# WL-FRONT.net
KiCad netlist of a schematic drawn in Altium Designer
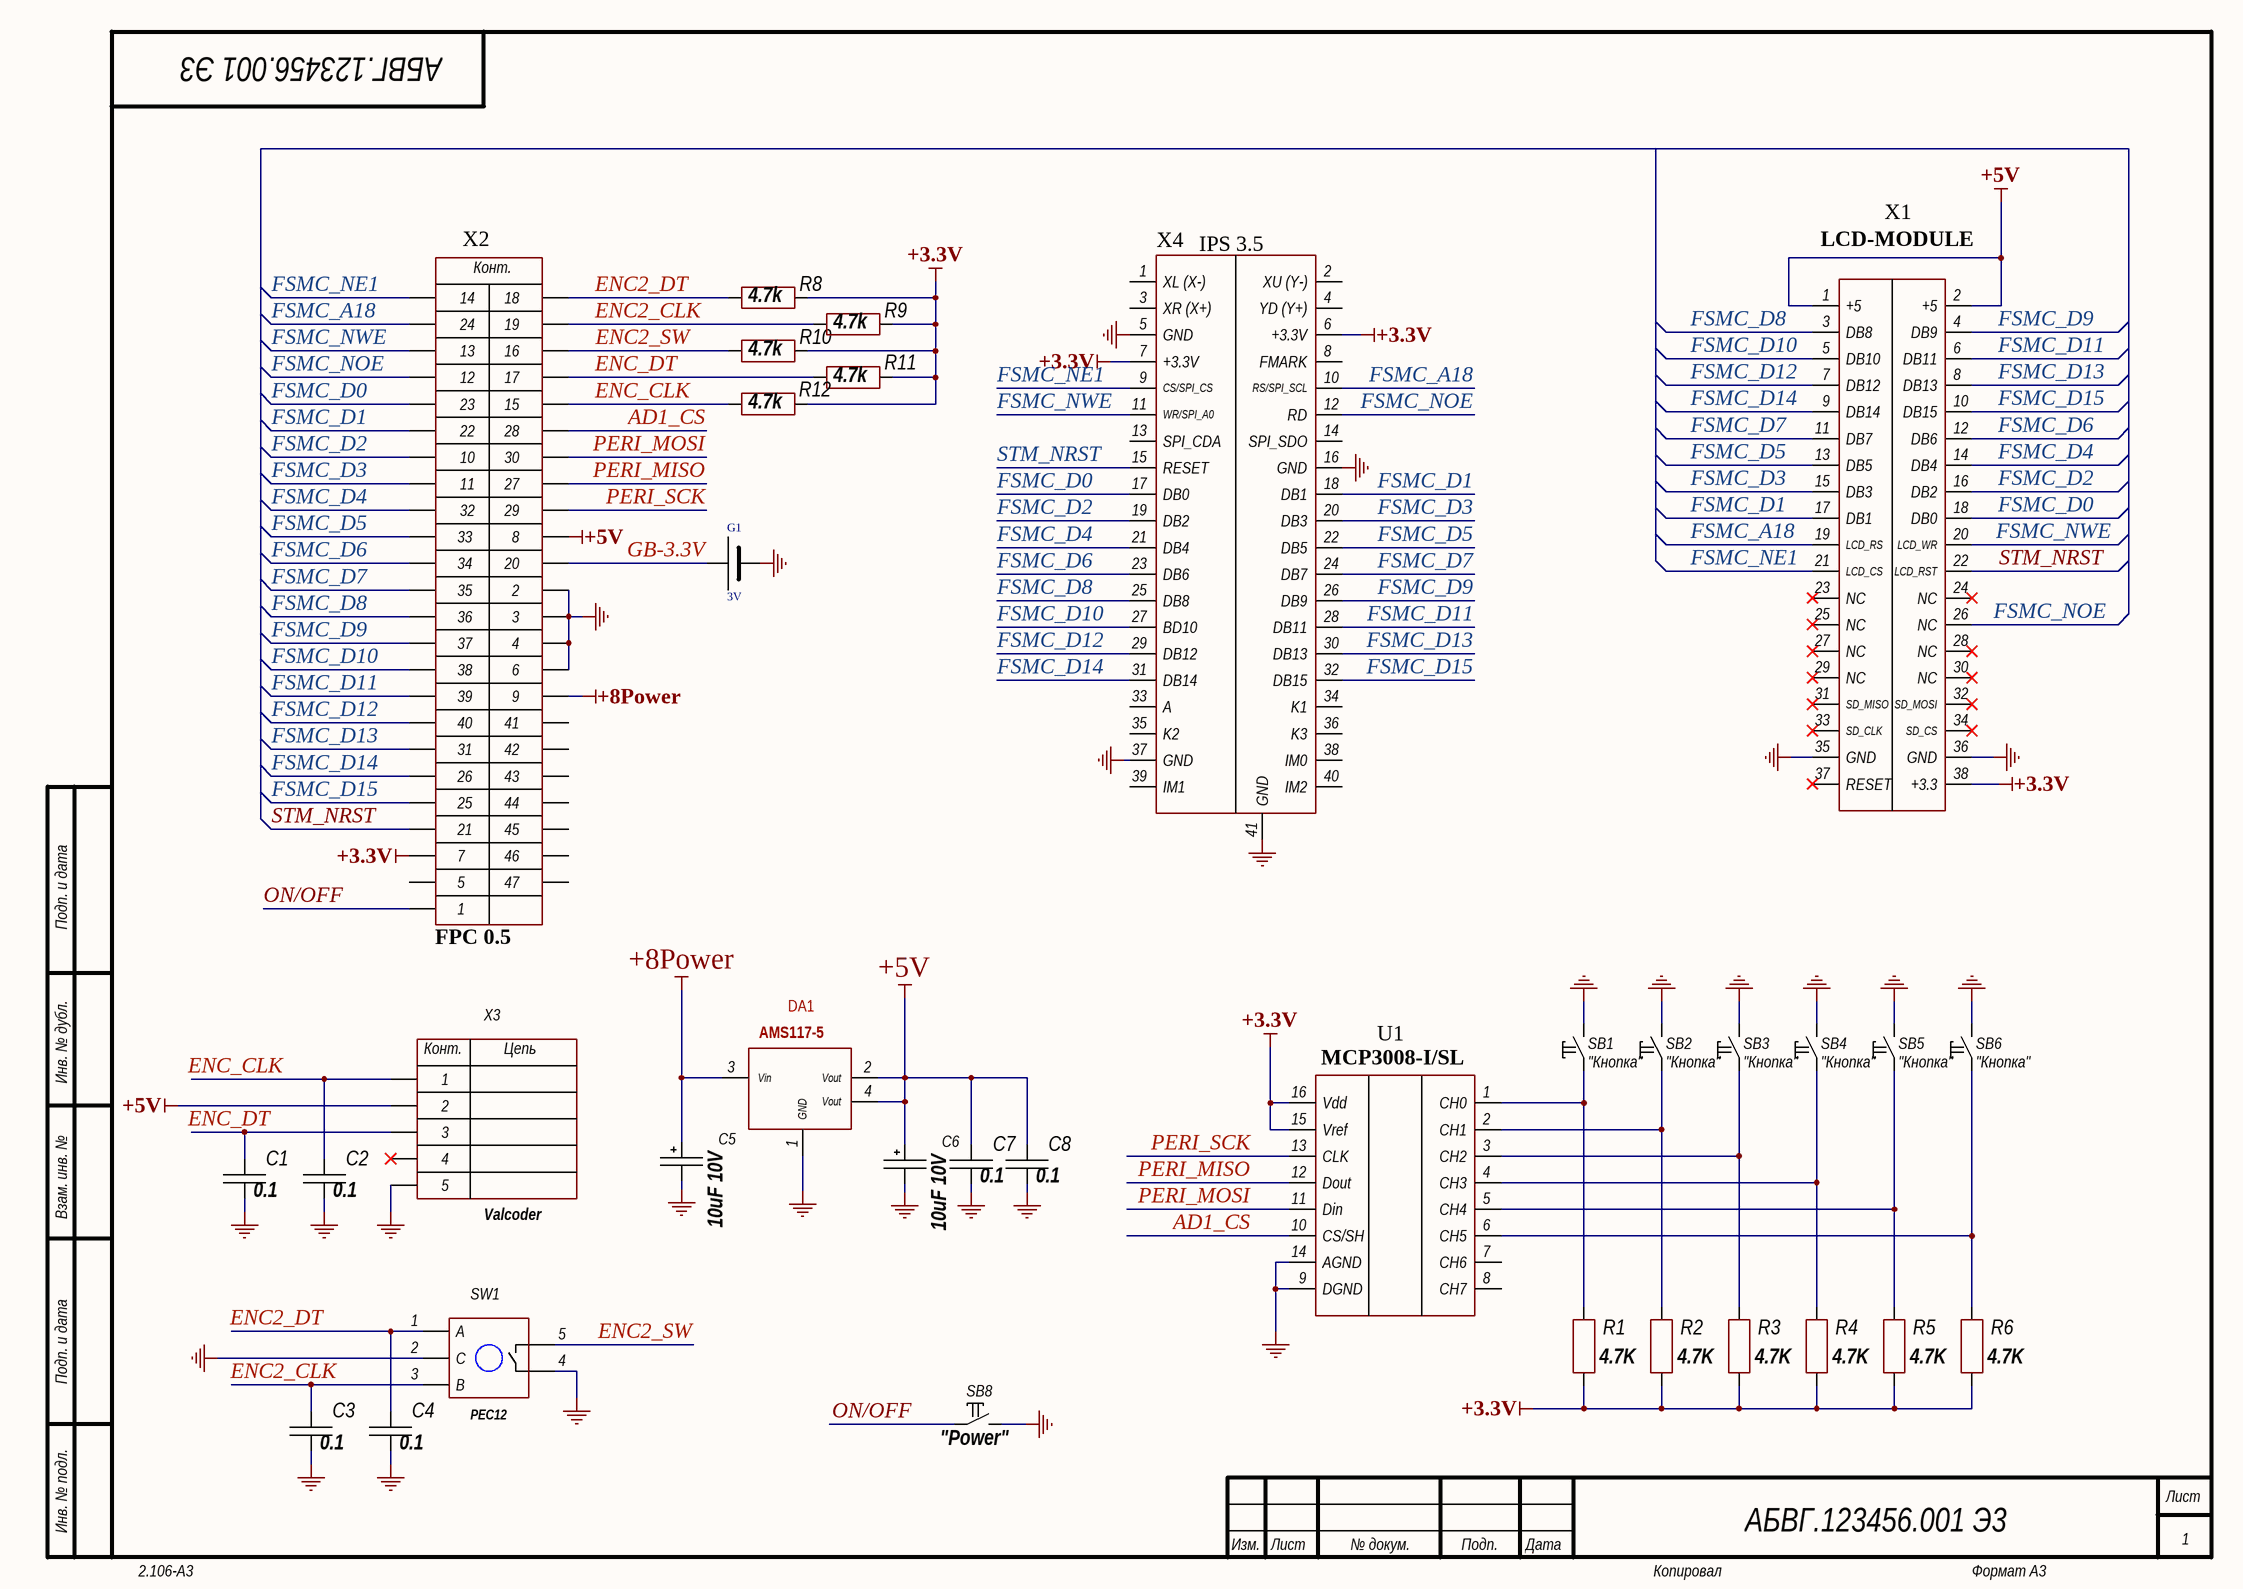
[diagram p0: WL-FRONT.SchDoc]

(export (version "E")
  (design (tool "Eeschema 10.0.6"))
  (components
    (comp (ref "C1")
      (value "0.1")
      (footprint "standard:CH0805C")
      (libsource (lib "Discrete") (part "Capacitor"))
    )
    (comp (ref "C2")
      (value "0.1")
      (footprint "standard:CH0805C")
      (libsource (lib "Discrete") (part "Capacitor"))
    )
    (comp (ref "C3")
      (value "0.1")
      (footprint "standard:CH0805C")
      (libsource (lib "Discrete") (part "Capacitor"))
    )
    (comp (ref "C4")
      (value "0.1")
      (footprint "standard:CH0805C")
      (libsource (lib "Discrete") (part "Capacitor"))
    )
    (comp (ref "C5")
      (value "10uF 10V")
      (footprint "standard:TANTAL_B")
      (libsource (lib "Discrete") (part "TantalCap"))
    )
    (comp (ref "C6")
      (value "10uF 10V")
      (footprint "standard:TANTAL_B")
      (libsource (lib "Discrete") (part "TantalCap"))
    )
    (comp (ref "C7")
      (value "0.1")
      (footprint "standard:CH0805C")
      (libsource (lib "Discrete") (part "Capacitor"))
    )
    (comp (ref "C8")
      (value "0.1")
      (footprint "standard:CH0805C")
      (libsource (lib "Discrete") (part "Capacitor"))
    )
    (comp (ref "DA1") (value "AMS117-5") (footprint "SOT223") (libsource (lib "Analog") (part "AMS117")))
    (comp (ref "G1")
      (value "3V")
      (footprint "BAT: CH224-2032")
      (libsource (lib "Connectors") (part "POWER_BAT"))
    )
    (comp (ref "R1")
      (value "4.7K")
      (footprint "standard:CH0805R")
      (libsource (lib "Discrete") (part "Resistor"))
    )
    (comp (ref "R2")
      (value "4.7K")
      (footprint "standard:CH0805R")
      (libsource (lib "Discrete") (part "Resistor"))
    )
    (comp (ref "R3") (value "4.7K") (footprint "standard:CH0805R") (libsource (lib "") (part "Resistor_2")))
    (comp (ref "R4")
      (value "4.7K")
      (footprint "standard:CH0805R")
      (libsource (lib "Discrete") (part "Resistor"))
    )
    (comp (ref "R5")
      (value "4.7K")
      (footprint "standard:CH0805R")
      (libsource (lib "Discrete") (part "Resistor"))
    )
    (comp (ref "R6")
      (value "4.7K")
      (footprint "standard:CH0805R")
      (libsource (lib "Discrete") (part "Resistor"))
    )
    (comp (ref "R8") (value "4.7k") (footprint "standard:CH0805R") (libsource (lib "") (part "Resistor_1")))
    (comp (ref "R9") (value "4.7k") (footprint "standard:CH0805R") (libsource (lib "") (part "Resistor_1")))
    (comp (ref "R10") (value "4.7k") (footprint "standard:CH0805R") (libsource (lib "") (part "Resistor_1")))
    (comp (ref "R11") (value "4.7k") (footprint "standard:CH0805R") (libsource (lib "") (part "Resistor_1")))
    (comp (ref "R12") (value "4.7k") (footprint "standard:CH0805R") (libsource (lib "") (part "Resistor_1")))
    (comp (ref "SB1")
      (value "\"Кнопка\"")
      (footprint "custom:BUT: 6x6 SMD")
      (description "6x6 mm")
      (libsource (lib "") (part "Tactile switches_1"))
    )
    (comp (ref "SB2")
      (value "\"Кнопка\"")
      (footprint "custom:BUT: 6x6 SMD")
      (description "6x6 mm")
      (libsource (lib "") (part "Tactile switches_1"))
    )
    (comp (ref "SB3")
      (value "\"Кнопка\"")
      (footprint "custom:BUT: 6x6 SMD")
      (description "6x6 mm")
      (libsource (lib "Connectors") (part "Tactile switches"))
    )
    (comp (ref "SB4")
      (value "\"Кнопка\"")
      (footprint "custom:BUT: 6x6 SMD")
      (description "6x6 mm")
      (libsource (lib "") (part "Tactile switches_1"))
    )
    (comp (ref "SB5")
      (value "\"Кнопка\"")
      (footprint "custom:BUT: 6x6 SMD")
      (description "6x6 mm")
      (libsource (lib "") (part "Tactile switches_1"))
    )
    (comp (ref "SB6")
      (value "\"Кнопка\"")
      (footprint "custom:BUT: 6x6 SMD")
      (description "6x6 mm")
      (libsource (lib "") (part "Tactile switches_1"))
    )
    (comp (ref "SB8")
      (value "\"Power\"")
      (footprint "custom:BUT: 6x6")
      (description "6x6 mm")
      (libsource (lib "") (part "Tactile switches_1"))
    )
    (comp (ref "SW1")
      (value "PEC12")
      (footprint "Valkoder-m2")
      (description "Encoder")
      (libsource (lib "Connectors") (part "PEC12"))
    )
    (comp (ref "U1")
      (value "MCP3008-I/SL")
      (footprint "16-SOIC")
      (libsource (lib "Digital") (part "MCP3008-I/SL"))
    )
    (comp (ref "X1")
      (value "LCD-MODULE")
      (footprint "TFT3.2-320x480-pin")
      (libsource (lib "Digital") (part "LCD-MODULE"))
    )
    (comp (ref "X2")
      (value "FPC 0.5")
      (footprint "CON: PBD2x20")
      (libsource (lib "Connectors") (part "FPC-45-0.5"))
    )
    (comp (ref "X3")
      (value "Valcoder")
      (footprint "custom:CON: PLS-5")
      (libsource (lib "Connectors") (part "5-Connector"))
    )
    (comp (ref "X4")
      (value "IPS 3.5")
      (footprint "IPS 3.5 ILI9481")
      (libsource (lib "Digital") (part "LCD-IPS 3.5"))
    )
  )
  (nets
    (net (code "1") (name "+3.3V") (class "Default")
      (node (ref "R1") (pin "1") (pinfunction "1_1") (pintype "passive"))
      (node (ref "R10") (pin "1") (pinfunction "1_1") (pintype "passive"))
      (node (ref "R11") (pin "1") (pinfunction "1_1") (pintype "passive"))
      (node (ref "R12") (pin "1") (pinfunction "1_1") (pintype "passive"))
      (node (ref "R2") (pin "1") (pinfunction "1_1") (pintype "passive"))
      (node (ref "R3") (pin "1") (pinfunction "1_1") (pintype "passive"))
      (node (ref "R4") (pin "1") (pinfunction "1_1") (pintype "passive"))
      (node (ref "R5") (pin "1") (pinfunction "1_1") (pintype "passive"))
      (node (ref "R6") (pin "1") (pinfunction "1_1") (pintype "passive"))
      (node (ref "R8") (pin "1") (pinfunction "1_1") (pintype "passive"))
      (node (ref "R9") (pin "1") (pinfunction "1_1") (pintype "passive"))
      (node (ref "U1") (pin "15") (pinfunction "Vref_15") (pintype "passive"))
      (node (ref "U1") (pin "16") (pinfunction "Vdd_16") (pintype "passive"))
      (node (ref "X1") (pin "38") (pinfunction "+3.3_38") (pintype "passive"))
      (node (ref "X2") (pin "7") (pinfunction "7_7") (pintype "power_in"))
      (node (ref "X4") (pin "6") (pinfunction "+3.3V_6") (pintype "passive"))
      (node (ref "X4") (pin "7") (pinfunction "+3.3V_7") (pintype "passive"))
    )
    (net (code "2") (name "+5V") (class "Default")
      (node (ref "C6") (pin "1") (pinfunction "1_1") (pintype "power_in"))
      (node (ref "C7") (pin "1") (pinfunction "1_1") (pintype "power_in"))
      (node (ref "C8") (pin "1") (pinfunction "1_1") (pintype "power_in"))
      (node (ref "DA1") (pin "2") (pinfunction "Vout_2") (pintype "passive"))
      (node (ref "DA1") (pin "4") (pinfunction "Vout_4") (pintype "passive"))
      (node (ref "X1") (pin "1") (pinfunction "+5_1") (pintype "passive"))
      (node (ref "X1") (pin "2") (pinfunction "+5_2") (pintype "passive"))
      (node (ref "X2") (pin "8") (pinfunction "8_8") (pintype "power_in"))
      (node (ref "X3") (pin "2") (pinfunction "2_2") (pintype "passive"))
    )
    (net (code "3") (name "+8Power") (class "Default")
      (node (ref "C5") (pin "1") (pinfunction "1_1") (pintype "power_in"))
      (node (ref "DA1") (pin "3") (pinfunction "Vin_3") (pintype "passive"))
      (node (ref "X2") (pin "9") (pinfunction "9_9") (pintype "power_in"))
    )
    (net (code "4") (name "/AD1_CS") (class "Default")
      (node (ref "U1") (pin "10") (pinfunction "CS/SH_10") (pintype "passive"))
      (node (ref "X2") (pin "28") (pinfunction "28_28") (pintype "power_in"))
    )
    (net (code "5") (name "/ENC2_CLK") (class "Default")
      (node (ref "C3") (pin "1") (pinfunction "1_1") (pintype "power_in"))
      (node (ref "R9") (pin "2") (pinfunction "2_2") (pintype "passive"))
      (node (ref "SW1") (pin "3") (pinfunction "B_3") (pintype "passive"))
      (node (ref "X2") (pin "19") (pinfunction "19_19") (pintype "power_in"))
    )
    (net (code "6") (name "/ENC2_DT") (class "Default")
      (node (ref "C4") (pin "1") (pinfunction "1_1") (pintype "power_in"))
      (node (ref "R8") (pin "2") (pinfunction "2_2") (pintype "passive"))
      (node (ref "SW1") (pin "1") (pinfunction "A_1") (pintype "passive"))
      (node (ref "X2") (pin "18") (pinfunction "18_18") (pintype "power_in"))
    )
    (net (code "7") (name "/ENC2_SW") (class "Default")
      (node (ref "R10") (pin "2") (pinfunction "2_2") (pintype "passive"))
      (node (ref "SW1") (pin "5") (pinfunction "5_5") (pintype "passive"))
      (node (ref "X2") (pin "16") (pinfunction "16_16") (pintype "power_in"))
    )
    (net (code "8") (name "/ENC_CLK") (class "Default")
      (node (ref "C2") (pin "1") (pinfunction "1_1") (pintype "power_in"))
      (node (ref "R12") (pin "2") (pinfunction "2_2") (pintype "passive"))
      (node (ref "X2") (pin "15") (pinfunction "15_15") (pintype "power_in"))
      (node (ref "X3") (pin "1") (pinfunction "1_1") (pintype "passive"))
    )
    (net (code "9") (name "/ENC_DT") (class "Default")
      (node (ref "C1") (pin "1") (pinfunction "1_1") (pintype "power_in"))
      (node (ref "R11") (pin "2") (pinfunction "2_2") (pintype "passive"))
      (node (ref "X2") (pin "17") (pinfunction "17_17") (pintype "power_in"))
      (node (ref "X3") (pin "3") (pinfunction "3_3") (pintype "power_in"))
    )
    (net (code "10") (name "/FSMC_A18") (class "Default")
      (node (ref "X1") (pin "19") (pinfunction "LCD_RS_19") (pintype "passive"))
      (node (ref "X2") (pin "24") (pinfunction "24_24") (pintype "passive"))
      (node (ref "X4") (pin "10") (pinfunction "RS/SPI_SCL_10") (pintype "passive"))
    )
    (net (code "11") (name "/FSMC_D0") (class "Default")
      (node (ref "X1") (pin "18") (pinfunction "DB0_18") (pintype "passive"))
      (node (ref "X2") (pin "23") (pinfunction "23_23") (pintype "power_in"))
      (node (ref "X4") (pin "17") (pinfunction "DB0_17") (pintype "passive"))
    )
    (net (code "12") (name "/FSMC_D1") (class "Default")
      (node (ref "X1") (pin "17") (pinfunction "DB1_17") (pintype "passive"))
      (node (ref "X2") (pin "22") (pinfunction "22_22") (pintype "power_in"))
      (node (ref "X4") (pin "18") (pinfunction "DB1_18") (pintype "passive"))
    )
    (net (code "13") (name "/FSMC_D2") (class "Default")
      (node (ref "X1") (pin "16") (pinfunction "DB2_16") (pintype "passive"))
      (node (ref "X2") (pin "10") (pinfunction "10_10") (pintype "power_in"))
      (node (ref "X4") (pin "19") (pinfunction "DB2_19") (pintype "passive"))
    )
    (net (code "14") (name "/FSMC_D3") (class "Default")
      (node (ref "X1") (pin "15") (pinfunction "DB3_15") (pintype "passive"))
      (node (ref "X2") (pin "11") (pinfunction "11_11") (pintype "power_in"))
      (node (ref "X4") (pin "20") (pinfunction "DB3_20") (pintype "passive"))
    )
    (net (code "15") (name "/FSMC_D4") (class "Default")
      (node (ref "X1") (pin "14") (pinfunction "DB4_14") (pintype "passive"))
      (node (ref "X2") (pin "32") (pinfunction "32_32") (pintype "power_in"))
      (node (ref "X4") (pin "21") (pinfunction "DB4_21") (pintype "passive"))
    )
    (net (code "16") (name "/FSMC_D5") (class "Default")
      (node (ref "X1") (pin "13") (pinfunction "DB5_13") (pintype "passive"))
      (node (ref "X2") (pin "33") (pinfunction "33_33") (pintype "power_in"))
      (node (ref "X4") (pin "22") (pinfunction "DB5_22") (pintype "passive"))
    )
    (net (code "17") (name "/FSMC_D6") (class "Default")
      (node (ref "X1") (pin "12") (pinfunction "DB6_12") (pintype "passive"))
      (node (ref "X2") (pin "34") (pinfunction "34_34") (pintype "power_in"))
      (node (ref "X4") (pin "23") (pinfunction "DB6_23") (pintype "passive"))
    )
    (net (code "18") (name "/FSMC_D7") (class "Default")
      (node (ref "X1") (pin "11") (pinfunction "DB7_11") (pintype "passive"))
      (node (ref "X2") (pin "35") (pinfunction "35_35") (pintype "power_in"))
      (node (ref "X4") (pin "24") (pinfunction "DB7_24") (pintype "passive"))
    )
    (net (code "19") (name "/FSMC_D8") (class "Default")
      (node (ref "X1") (pin "3") (pinfunction "DB8_3") (pintype "passive"))
      (node (ref "X2") (pin "36") (pinfunction "36_36") (pintype "power_in"))
      (node (ref "X4") (pin "25") (pinfunction "DB8_25") (pintype "passive"))
    )
    (net (code "20") (name "/FSMC_D9") (class "Default")
      (node (ref "X1") (pin "4") (pinfunction "DB9_4") (pintype "passive"))
      (node (ref "X2") (pin "37") (pinfunction "37_37") (pintype "power_in"))
      (node (ref "X4") (pin "26") (pinfunction "DB9_26") (pintype "passive"))
    )
    (net (code "21") (name "/FSMC_D10") (class "Default")
      (node (ref "X1") (pin "5") (pinfunction "DB10_5") (pintype "passive"))
      (node (ref "X2") (pin "38") (pinfunction "38_38") (pintype "power_in"))
      (node (ref "X4") (pin "27") (pinfunction "BD10_27") (pintype "passive"))
    )
    (net (code "22") (name "/FSMC_D11") (class "Default")
      (node (ref "X1") (pin "6") (pinfunction "DB11_6") (pintype "passive"))
      (node (ref "X2") (pin "39") (pinfunction "39_39") (pintype "power_in"))
      (node (ref "X4") (pin "28") (pinfunction "DB11_28") (pintype "passive"))
    )
    (net (code "23") (name "/FSMC_D12") (class "Default")
      (node (ref "X1") (pin "7") (pinfunction "DB12_7") (pintype "passive"))
      (node (ref "X2") (pin "40") (pinfunction "40_40") (pintype "power_in"))
      (node (ref "X4") (pin "29") (pinfunction "DB12_29") (pintype "passive"))
    )
    (net (code "24") (name "/FSMC_D13") (class "Default")
      (node (ref "X1") (pin "8") (pinfunction "DB13_8") (pintype "passive"))
      (node (ref "X2") (pin "31") (pinfunction "31_31") (pintype "power_in"))
      (node (ref "X4") (pin "30") (pinfunction "DB13_30") (pintype "passive"))
    )
    (net (code "25") (name "/FSMC_D14") (class "Default")
      (node (ref "X1") (pin "9") (pinfunction "DB14_9") (pintype "passive"))
      (node (ref "X2") (pin "26") (pinfunction "26_26") (pintype "power_in"))
      (node (ref "X4") (pin "31") (pinfunction "DB14_31") (pintype "passive"))
    )
    (net (code "26") (name "/FSMC_D15") (class "Default")
      (node (ref "X1") (pin "10") (pinfunction "DB15_10") (pintype "passive"))
      (node (ref "X2") (pin "25") (pinfunction "25_25") (pintype "power_in"))
      (node (ref "X4") (pin "32") (pinfunction "DB15_32") (pintype "passive"))
    )
    (net (code "27") (name "/FSMC_NE1") (class "Default")
      (node (ref "X1") (pin "21") (pinfunction "LCD_CS_21") (pintype "passive"))
      (node (ref "X2") (pin "14") (pinfunction "14_14") (pintype "passive"))
      (node (ref "X4") (pin "9") (pinfunction "CS/SPI_CS_9") (pintype "passive"))
    )
    (net (code "28") (name "/FSMC_NOE") (class "Default")
      (node (ref "X1") (pin "26") (pinfunction "NC_26") (pintype "passive"))
      (node (ref "X2") (pin "12") (pinfunction "12_12") (pintype "power_in"))
      (node (ref "X4") (pin "12") (pinfunction "RD_12") (pintype "passive"))
    )
    (net (code "29") (name "/FSMC_NWE") (class "Default")
      (node (ref "X1") (pin "20") (pinfunction "LCD_WR_20") (pintype "passive"))
      (node (ref "X2") (pin "13") (pinfunction "13_13") (pintype "power_in"))
      (node (ref "X4") (pin "11") (pinfunction "WR/SPI_A0_11") (pintype "passive"))
    )
    (net (code "30") (name "/GB-3.3V") (class "Default")
      (node (ref "G1") (pin "1") (pinfunction "0_1") (pintype "passive"))
      (node (ref "X2") (pin "20") (pinfunction "20_20") (pintype "power_in"))
    )
    (net (code "31") (name "/ON{slash}OFF") (class "Default")
      (node (ref "SB8") (pin "1") (pinfunction "1_1") (pintype "passive"))
      (node (ref "X2") (pin "1") (pinfunction "1_1") (pintype "power_in"))
    )
    (net (code "32") (name "/PERI_MISO") (class "Default")
      (node (ref "U1") (pin "12") (pinfunction "Dout_12") (pintype "passive"))
      (node (ref "X2") (pin "27") (pinfunction "27_27") (pintype "power_in"))
    )
    (net (code "33") (name "/PERI_MOSI") (class "Default")
      (node (ref "U1") (pin "11") (pinfunction "Din_11") (pintype "passive"))
      (node (ref "X2") (pin "30") (pinfunction "30_30") (pintype "power_in"))
    )
    (net (code "34") (name "/PERI_SCK") (class "Default")
      (node (ref "U1") (pin "13") (pinfunction "CLK_13") (pintype "passive"))
      (node (ref "X2") (pin "29") (pinfunction "29_29") (pintype "power_in"))
    )
    (net (code "35") (name "/STM_NRST") (class "Default")
      (node (ref "X1") (pin "22") (pinfunction "LCD_RST_22") (pintype "passive"))
      (node (ref "X2") (pin "21") (pinfunction "21_21") (pintype "power_in"))
      (node (ref "X4") (pin "15") (pinfunction "RESET_15") (pintype "passive"))
    )
    (net (code "36") (name "GND") (class "Default")
      (node (ref "C1") (pin "2") (pinfunction "2_2") (pintype "power_in"))
      (node (ref "C2") (pin "2") (pinfunction "2_2") (pintype "power_in"))
      (node (ref "C3") (pin "2") (pinfunction "2_2") (pintype "power_in"))
      (node (ref "C4") (pin "2") (pinfunction "2_2") (pintype "power_in"))
      (node (ref "C5") (pin "2") (pinfunction "2_2") (pintype "power_in"))
      (node (ref "C6") (pin "2") (pinfunction "2_2") (pintype "power_in"))
      (node (ref "C7") (pin "2") (pinfunction "2_2") (pintype "power_in"))
      (node (ref "C8") (pin "2") (pinfunction "2_2") (pintype "power_in"))
      (node (ref "DA1") (pin "1") (pinfunction "GND_1") (pintype "passive"))
      (node (ref "G1") (pin "2") (pinfunction "1_2") (pintype "passive"))
      (node (ref "SB1") (pin "2") (pinfunction "2_2") (pintype "passive"))
      (node (ref "SB2") (pin "2") (pinfunction "2_2") (pintype "passive"))
      (node (ref "SB3") (pin "2") (pinfunction "2_2") (pintype "passive"))
      (node (ref "SB4") (pin "2") (pinfunction "2_2") (pintype "passive"))
      (node (ref "SB5") (pin "2") (pinfunction "2_2") (pintype "passive"))
      (node (ref "SB6") (pin "2") (pinfunction "2_2") (pintype "passive"))
      (node (ref "SB8") (pin "2") (pinfunction "2_2") (pintype "passive"))
      (node (ref "SW1") (pin "2") (pinfunction "C_2") (pintype "passive"))
      (node (ref "SW1") (pin "4") (pinfunction "4_4") (pintype "passive"))
      (node (ref "U1") (pin "14") (pinfunction "AGND_14") (pintype "passive"))
      (node (ref "U1") (pin "9") (pinfunction "DGND_9") (pintype "passive"))
      (node (ref "X1") (pin "35") (pinfunction "GND_35") (pintype "passive"))
      (node (ref "X1") (pin "36") (pinfunction "GND_36") (pintype "passive"))
      (node (ref "X2") (pin "2") (pinfunction "2_2") (pintype "power_in"))
      (node (ref "X2") (pin "3") (pinfunction "3_3") (pintype "power_in"))
      (node (ref "X2") (pin "4") (pinfunction "4_4") (pintype "power_in"))
      (node (ref "X2") (pin "6") (pinfunction "6_6") (pintype "power_in"))
      (node (ref "X3") (pin "5") (pinfunction "5_5") (pintype "power_in"))
      (node (ref "X4") (pin "16") (pinfunction "GND_16") (pintype "passive"))
      (node (ref "X4") (pin "37") (pinfunction "GND_37") (pintype "passive"))
      (node (ref "X4") (pin "41") (pinfunction "GND_41") (pintype "passive"))
      (node (ref "X4") (pin "5") (pinfunction "GND_5") (pintype "passive"))
    )
    (net (code "37") (name "Net-(U1-CH0)") (class "Default")
      (node (ref "R1") (pin "2") (pinfunction "2_2") (pintype "passive"))
      (node (ref "SB1") (pin "1") (pinfunction "1_1") (pintype "passive"))
      (node (ref "U1") (pin "1") (pinfunction "CH0_1") (pintype "passive"))
    )
    (net (code "38") (name "Net-(U1-CH1)") (class "Default")
      (node (ref "R2") (pin "2") (pinfunction "2_2") (pintype "passive"))
      (node (ref "SB2") (pin "1") (pinfunction "1_1") (pintype "passive"))
      (node (ref "U1") (pin "2") (pinfunction "CH1_2") (pintype "passive"))
    )
    (net (code "39") (name "Net-(U1-CH2)") (class "Default")
      (node (ref "R3") (pin "2") (pinfunction "2_2") (pintype "passive"))
      (node (ref "SB3") (pin "1") (pinfunction "1_1") (pintype "passive"))
      (node (ref "U1") (pin "3") (pinfunction "CH2_3") (pintype "passive"))
    )
    (net (code "40") (name "Net-(U1-CH3)") (class "Default")
      (node (ref "R4") (pin "2") (pinfunction "2_2") (pintype "passive"))
      (node (ref "SB4") (pin "1") (pinfunction "1_1") (pintype "passive"))
      (node (ref "U1") (pin "4") (pinfunction "CH3_4") (pintype "passive"))
    )
    (net (code "41") (name "Net-(U1-CH4)") (class "Default")
      (node (ref "R5") (pin "2") (pinfunction "2_2") (pintype "passive"))
      (node (ref "SB5") (pin "1") (pinfunction "1_1") (pintype "passive"))
      (node (ref "U1") (pin "5") (pinfunction "CH4_5") (pintype "passive"))
    )
    (net (code "42") (name "Net-(U1-CH5)") (class "Default")
      (node (ref "R6") (pin "2") (pinfunction "2_2") (pintype "passive"))
      (node (ref "SB6") (pin "1") (pinfunction "1_1") (pintype "passive"))
      (node (ref "U1") (pin "6") (pinfunction "CH5_6") (pintype "passive"))
    )
    (net (code "43") (name "unconnected-(U1-CH6-Pad7)") (class "Default")
      (node (ref "U1") (pin "7") (pinfunction "CH6_7") (pintype "passive"))
    )
    (net (code "44") (name "unconnected-(U1-CH7-Pad8)") (class "Default")
      (node (ref "U1") (pin "8") (pinfunction "CH7_8") (pintype "passive"))
    )
    (net (code "45") (name "unconnected-(X1-NC-Pad23)") (class "Default")
      (node (ref "X1") (pin "23") (pinfunction "NC_23") (pintype "passive+no_connect"))
    )
    (net (code "46") (name "unconnected-(X1-NC-Pad24)") (class "Default")
      (node (ref "X1") (pin "24") (pinfunction "NC_24") (pintype "passive+no_connect"))
    )
    (net (code "47") (name "unconnected-(X1-NC-Pad25)") (class "Default")
      (node (ref "X1") (pin "25") (pinfunction "NC_25") (pintype "passive+no_connect"))
    )
    (net (code "48") (name "unconnected-(X1-NC-Pad27)") (class "Default")
      (node (ref "X1") (pin "27") (pinfunction "NC_27") (pintype "passive+no_connect"))
    )
    (net (code "49") (name "unconnected-(X1-NC-Pad28)") (class "Default")
      (node (ref "X1") (pin "28") (pinfunction "NC_28") (pintype "passive+no_connect"))
    )
    (net (code "50") (name "unconnected-(X1-NC-Pad29)") (class "Default")
      (node (ref "X1") (pin "29") (pinfunction "NC_29") (pintype "passive+no_connect"))
    )
    (net (code "51") (name "unconnected-(X1-NC-Pad30)") (class "Default")
      (node (ref "X1") (pin "30") (pinfunction "NC_30") (pintype "passive+no_connect"))
    )
    (net (code "52") (name "unconnected-(X1-RESET-Pad37)") (class "Default")
      (node (ref "X1") (pin "37") (pinfunction "RESET_37") (pintype "passive+no_connect"))
    )
    (net (code "53") (name "unconnected-(X1-SD_CLK-Pad33)") (class "Default")
      (node (ref "X1") (pin "33") (pinfunction "SD_CLK_33") (pintype "passive+no_connect"))
    )
    (net (code "54") (name "unconnected-(X1-SD_CS-Pad34)") (class "Default")
      (node (ref "X1") (pin "34") (pinfunction "SD_CS_34") (pintype "passive+no_connect"))
    )
    (net (code "55") (name "unconnected-(X1-SD_MISO-Pad31)") (class "Default")
      (node (ref "X1") (pin "31") (pinfunction "SD_MISO_31") (pintype "passive+no_connect"))
    )
    (net (code "56") (name "unconnected-(X1-SD_MOSI-Pad32)") (class "Default")
      (node (ref "X1") (pin "32") (pinfunction "SD_MOSI_32") (pintype "passive+no_connect"))
    )
    (net (code "57") (name "unconnected-(X2-Pad5)") (class "Default")
      (node (ref "X2") (pin "5") (pinfunction "5_5") (pintype "power_in"))
    )
    (net (code "58") (name "unconnected-(X2-Pad41)") (class "Default")
      (node (ref "X2") (pin "41") (pinfunction "41_41") (pintype "power_in"))
    )
    (net (code "59") (name "unconnected-(X2-Pad42)") (class "Default")
      (node (ref "X2") (pin "42") (pinfunction "42_42") (pintype "power_in"))
    )
    (net (code "60") (name "unconnected-(X2-Pad43)") (class "Default")
      (node (ref "X2") (pin "43") (pinfunction "43_43") (pintype "power_in"))
    )
    (net (code "61") (name "unconnected-(X2-Pad44)") (class "Default")
      (node (ref "X2") (pin "44") (pinfunction "44_44") (pintype "power_in"))
    )
    (net (code "62") (name "unconnected-(X2-Pad45)") (class "Default")
      (node (ref "X2") (pin "45") (pinfunction "45_45") (pintype "power_in"))
    )
    (net (code "63") (name "unconnected-(X2-Pad46)") (class "Default")
      (node (ref "X2") (pin "46") (pinfunction "46_46") (pintype "power_in"))
    )
    (net (code "64") (name "unconnected-(X2-Pad47)") (class "Default")
      (node (ref "X2") (pin "47") (pinfunction "47_47") (pintype "power_in"))
    )
    (net (code "65") (name "unconnected-(X3-Pad4)") (class "Default")
      (node (ref "X3") (pin "4") (pinfunction "4_4") (pintype "power_in+no_connect"))
    )
    (net (code "66") (name "unconnected-(X4-A-Pad33)") (class "Default")
      (node (ref "X4") (pin "33") (pinfunction "A_33") (pintype "passive"))
    )
    (net (code "67") (name "unconnected-(X4-FMARK-Pad8)") (class "Default")
      (node (ref "X4") (pin "8") (pinfunction "FMARK_8") (pintype "passive"))
    )
    (net (code "68") (name "unconnected-(X4-IM0-Pad38)") (class "Default")
      (node (ref "X4") (pin "38") (pinfunction "IM0_38") (pintype "passive"))
    )
    (net (code "69") (name "unconnected-(X4-IM1-Pad39)") (class "Default")
      (node (ref "X4") (pin "39") (pinfunction "IM1_39") (pintype "passive"))
    )
    (net (code "70") (name "unconnected-(X4-IM2-Pad40)") (class "Default")
      (node (ref "X4") (pin "40") (pinfunction "IM2_40") (pintype "passive"))
    )
    (net (code "71") (name "unconnected-(X4-K1-Pad34)") (class "Default")
      (node (ref "X4") (pin "34") (pinfunction "K1_34") (pintype "passive"))
    )
    (net (code "72") (name "unconnected-(X4-K2-Pad35)") (class "Default")
      (node (ref "X4") (pin "35") (pinfunction "K2_35") (pintype "passive"))
    )
    (net (code "73") (name "unconnected-(X4-K3-Pad36)") (class "Default")
      (node (ref "X4") (pin "36") (pinfunction "K3_36") (pintype "passive"))
    )
    (net (code "74") (name "unconnected-(X4-SPI_CDA-Pad13)") (class "Default")
      (node (ref "X4") (pin "13") (pinfunction "SPI_CDA_13") (pintype "passive"))
    )
    (net (code "75") (name "unconnected-(X4-SPI_SDO-Pad14)") (class "Default")
      (node (ref "X4") (pin "14") (pinfunction "SPI_SDO_14") (pintype "passive"))
    )
    (net (code "76") (name "unconnected-(X4-XL_(X-)-Pad1)") (class "Default")
      (node (ref "X4") (pin "1") (pinfunction "XL_(X-)_1") (pintype "passive"))
    )
    (net (code "77") (name "unconnected-(X4-XR_(X+)-Pad3)") (class "Default")
      (node (ref "X4") (pin "3") (pinfunction "XR_(X+)_3") (pintype "passive"))
    )
    (net (code "78") (name "unconnected-(X4-XU_(Y-)-Pad2)") (class "Default")
      (node (ref "X4") (pin "2") (pinfunction "XU_(Y-)_2") (pintype "passive"))
    )
    (net (code "79") (name "unconnected-(X4-YD_(Y+)-Pad4)") (class "Default")
      (node (ref "X4") (pin "4") (pinfunction "YD_(Y+)_4") (pintype "passive"))
    )
  )
)
